# T-Board-44-84_PCB_-_v0_1.net
KiCad netlist of a schematic drawn in EAGLE
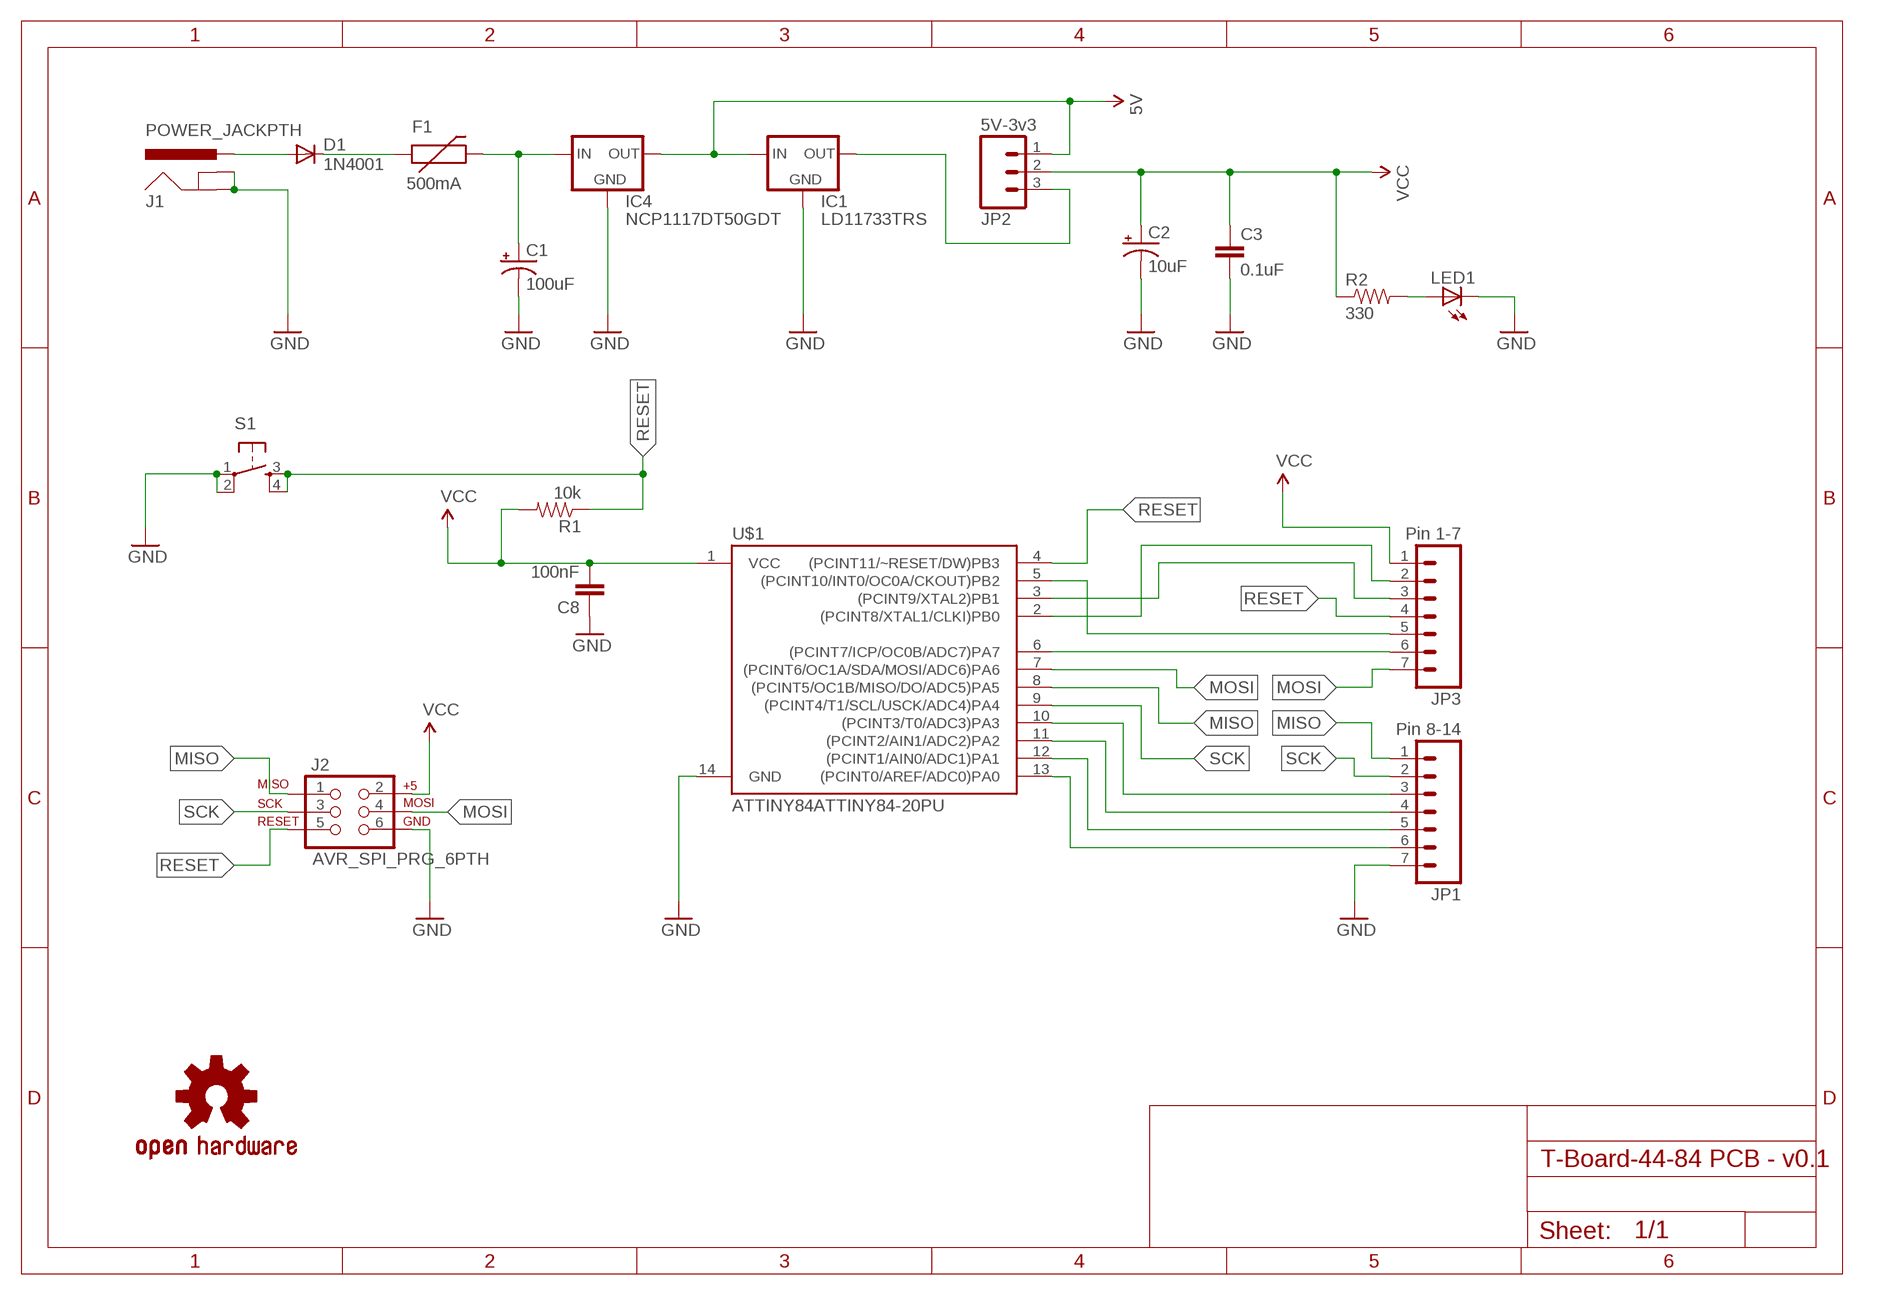
[diagram p0: schematic, sheet 1]

(export (version "E")
  (design (tool "Eeschema 10.0.6"))
  (components
    (comp (ref "C1")
      (value "100uF")
      (footprint "eagle-import:CPOL-RADIAL-100UF-25V")
      (libsource (lib "eagle-import") (part "CAP_POLPTH1"))
    )
    (comp (ref "C2")
      (value "10uF")
      (footprint "eagle-import:CPOL-RADIAL-10UF-25V")
      (libsource (lib "eagle-import") (part "CAP_POLPTH2"))
    )
    (comp (ref "C3")
      (value "0.1uF")
      (footprint "eagle-import:1206")
      (libsource (lib "eagle-import") (part "CAP1206"))
    )
    (comp (ref "C8")
      (value "100nF")
      (footprint "eagle-import:1206")
      (libsource (lib "eagle-import") (part "CAP1206"))
    )
    (comp (ref "D1")
      (value "1N4001")
      (footprint "eagle-import:DIODE-1N4001")
      (libsource (lib "eagle-import") (part "DIODEPTH"))
    )
    (comp (ref "F1")
      (value "500mA")
      (footprint "eagle-import:PTC")
      (libsource (lib "eagle-import") (part "PTCPTH"))
    )
    (comp (ref "IC1")
      (value "LD11733TRS")
      (footprint "eagle-import:SOT223")
      (libsource (lib "eagle-import") (part "LD117S33TR"))
    )
    (comp (ref "IC4")
      (value "NCP1117DT50GDT")
      (footprint "eagle-import:DPACK")
      (libsource (lib "eagle-import") (part "NCP1117DTDT50G"))
    )
    (comp (ref "J1")
      (value "POWER_JACKPTH")
      (footprint "eagle-import:POWER_JACK_PTH")
      (libsource (lib "eagle-import") (part "POWER_JACKPTH"))
    )
    (comp (ref "J2")
      (value "AVR_SPI_PRG_6PTH")
      (footprint "eagle-import:2X3")
      (libsource (lib "eagle-import") (part "AVR_SPI_PRG_6PTH"))
    )
    (comp (ref "JP1")
      (value "Pin 8-14")
      (footprint "eagle-import:1X07")
      (libsource (lib "eagle-import") (part "M07"))
    )
    (comp (ref "JP2")
      (value "5V-3v3")
      (footprint "eagle-import:1X03")
      (libsource (lib "eagle-import") (part "M03PTH"))
    )
    (comp (ref "JP3")
      (value "Pin 1-7")
      (footprint "eagle-import:1X07")
      (libsource (lib "eagle-import") (part "M07"))
    )
    (comp (ref "LED1")
      (value "LED1206")
      (footprint "eagle-import:LED-1206")
      (libsource (lib "eagle-import") (part "LED1206"))
    )
    (comp (ref "LOGO1")
      (value "OSHW-LOGOS")
      (footprint "eagle-import:OSHW-LOGO-S")
      (libsource (lib "eagle-import") (part "OSHW-LOGOS"))
    )
    (comp (ref "R1")
      (value "10k")
      (footprint "eagle-import:1206")
      (libsource (lib "eagle-import") (part "RESISTOR1206"))
    )
    (comp (ref "R2")
      (value "330")
      (footprint "eagle-import:1206")
      (libsource (lib "eagle-import") (part "RESISTOR1206"))
    )
    (comp (ref "S1")
      (value "TAC_SWITCHPTH")
      (footprint "eagle-import:TACTILE-PTH")
      (libsource (lib "eagle-import") (part "TAC_SWITCHPTH"))
    )
    (comp (ref "U$1")
      (value "ATTINY84ATTINY84-20PU")
      (footprint "eagle-import:DIL14")
      (libsource (lib "eagle-import") (part "ATTINY84ATTINY84-20PU"))
    )
  )
  (nets
    (net (code "1") (name "5V") (class "Default")
      (node (ref "IC1") (pin "3") (pinfunction "IN_3") (pintype "input"))
      (node (ref "IC4") (pin "4") (pinfunction "OUT_4") (pintype "passive"))
      (node (ref "JP2") (pin "1") (pinfunction "1_1") (pintype "passive"))
    )
    (net (code "2") (name "GND") (class "Default")
      (node (ref "C1") (pin "2") (pinfunction "-_2") (pintype "passive"))
      (node (ref "C2") (pin "2") (pinfunction "-_2") (pintype "passive"))
      (node (ref "C3") (pin "2") (pinfunction "2_2") (pintype "passive"))
      (node (ref "C8") (pin "1") (pinfunction "1_1") (pintype "passive"))
      (node (ref "IC1") (pin "1") (pinfunction "GND_1") (pintype "input"))
      (node (ref "IC4") (pin "1") (pinfunction "GND_1") (pintype "input"))
      (node (ref "J1") (pin "GND") (pinfunction "GND_GND") (pintype "bidirectional"))
      (node (ref "J1") (pin "GNDBREAK") (pinfunction "GNDBREAK_GNDBREAK") (pintype "bidirectional"))
      (node (ref "J2") (pin "6") (pinfunction "6_6") (pintype "passive"))
      (node (ref "JP1") (pin "7") (pinfunction "7_7") (pintype "passive"))
      (node (ref "LED1") (pin "C") (pinfunction "C_C") (pintype "passive"))
      (node (ref "S1") (pin "1") (pinfunction "1_1") (pintype "passive"))
      (node (ref "S1") (pin "2") (pinfunction "2_2") (pintype "passive"))
      (node (ref "U$1") (pin "14") (pinfunction "GND_14") (pintype "bidirectional"))
    )
    (net (code "3") (name "MISO") (class "Default")
      (node (ref "J2") (pin "1") (pinfunction "1_1") (pintype "passive"))
      (node (ref "JP1") (pin "1") (pinfunction "1_1") (pintype "passive"))
      (node (ref "U$1") (pin "8") (pinfunction "(PCINT5/OC1B/MISO/DO/ADC5)PA5_8") (pintype "bidirectional"))
    )
    (net (code "4") (name "MOSI") (class "Default")
      (node (ref "J2") (pin "4") (pinfunction "4_4") (pintype "passive"))
      (node (ref "JP3") (pin "7") (pinfunction "7_7") (pintype "passive"))
      (node (ref "U$1") (pin "7") (pinfunction "(PCINT6/OC1A/SDA/MOSI/ADC6)PA6_7") (pintype "bidirectional"))
    )
    (net (code "5") (name "Net-(C1-+)") (class "Default")
      (node (ref "C1") (pin "1") (pinfunction "+_1") (pintype "passive"))
      (node (ref "F1") (pin "P$2") (pinfunction "2_P$2") (pintype "bidirectional"))
      (node (ref "IC4") (pin "3") (pinfunction "IN_3") (pintype "input"))
    )
    (net (code "6") (name "Net-(D1-PadA)") (class "Default")
      (node (ref "D1") (pin "A") (pinfunction "A_A") (pintype "passive"))
      (node (ref "J1") (pin "PWR") (pinfunction "PWR_PWR") (pintype "bidirectional"))
    )
    (net (code "7") (name "Net-(F1-1)") (class "Default")
      (node (ref "D1") (pin "C") (pinfunction "C_C") (pintype "passive"))
      (node (ref "F1") (pin "P$1") (pinfunction "1_P$1") (pintype "bidirectional"))
    )
    (net (code "8") (name "Net-(IC1-OUT)") (class "Default")
      (node (ref "IC1") (pin "4") (pinfunction "OUT_4") (pintype "passive"))
      (node (ref "JP2") (pin "3") (pinfunction "3_3") (pintype "passive"))
    )
    (net (code "9") (name "Net-(LED1-PadA)") (class "Default")
      (node (ref "LED1") (pin "A") (pinfunction "A_A") (pintype "passive"))
      (node (ref "R2") (pin "2") (pinfunction "2_2") (pintype "passive"))
    )
    (net (code "10") (name "Net-(U$1-(PCINT0{slash}AREF{slash}ADC0)PA0)") (class "Default")
      (node (ref "JP1") (pin "6") (pinfunction "6_6") (pintype "passive"))
      (node (ref "U$1") (pin "13") (pinfunction "(PCINT0/AREF/ADC0)PA0_13") (pintype "bidirectional"))
    )
    (net (code "11") (name "Net-(U$1-(PCINT1{slash}AIN0{slash}ADC1)PA1)") (class "Default")
      (node (ref "JP1") (pin "5") (pinfunction "5_5") (pintype "passive"))
      (node (ref "U$1") (pin "12") (pinfunction "(PCINT1/AIN0/ADC1)PA1_12") (pintype "bidirectional"))
    )
    (net (code "12") (name "Net-(U$1-(PCINT2{slash}AIN1{slash}ADC2)PA2)") (class "Default")
      (node (ref "JP1") (pin "4") (pinfunction "4_4") (pintype "passive"))
      (node (ref "U$1") (pin "11") (pinfunction "(PCINT2/AIN1/ADC2)PA2_11") (pintype "bidirectional"))
    )
    (net (code "13") (name "Net-(U$1-(PCINT3{slash}T0{slash}ADC3)PA3)") (class "Default")
      (node (ref "JP1") (pin "3") (pinfunction "3_3") (pintype "passive"))
      (node (ref "U$1") (pin "10") (pinfunction "(PCINT3/T0/ADC3)PA3_10") (pintype "bidirectional"))
    )
    (net (code "14") (name "Net-(U$1-(PCINT7{slash}ICP{slash}OC0B{slash}ADC7)PA7)") (class "Default")
      (node (ref "JP3") (pin "6") (pinfunction "6_6") (pintype "passive"))
      (node (ref "U$1") (pin "6") (pinfunction "(PCINT7/ICP/OC0B/ADC7)PA7_6") (pintype "bidirectional"))
    )
    (net (code "15") (name "Net-(U$1-(PCINT8{slash}XTAL1{slash}CLKI)PB0)") (class "Default")
      (node (ref "JP3") (pin "2") (pinfunction "2_2") (pintype "passive"))
      (node (ref "U$1") (pin "2") (pinfunction "(PCINT8/XTAL1/CLKI)PB0_2") (pintype "bidirectional"))
    )
    (net (code "16") (name "Net-(U$1-(PCINT9{slash}XTAL2)PB1)") (class "Default")
      (node (ref "JP3") (pin "3") (pinfunction "3_3") (pintype "passive"))
      (node (ref "U$1") (pin "3") (pinfunction "(PCINT9/XTAL2)PB1_3") (pintype "bidirectional"))
    )
    (net (code "17") (name "Net-(U$1-(PCINT10{slash}INT0{slash}OC0A{slash}CKOUT)PB2)") (class "Default")
      (node (ref "JP3") (pin "5") (pinfunction "5_5") (pintype "passive"))
      (node (ref "U$1") (pin "5") (pinfunction "(PCINT10/INT0/OC0A/CKOUT)PB2_5") (pintype "bidirectional"))
    )
    (net (code "18") (name "RESET") (class "Default")
      (node (ref "J2") (pin "5") (pinfunction "5_5") (pintype "passive"))
      (node (ref "JP3") (pin "4") (pinfunction "4_4") (pintype "passive"))
      (node (ref "R1") (pin "1") (pinfunction "1_1") (pintype "passive"))
      (node (ref "S1") (pin "3") (pinfunction "3_3") (pintype "passive"))
      (node (ref "S1") (pin "4") (pinfunction "4_4") (pintype "passive"))
      (node (ref "U$1") (pin "4") (pinfunction "(PCINT11/~{RESET/DW})PB3_4") (pintype "bidirectional"))
    )
    (net (code "19") (name "SCK") (class "Default")
      (node (ref "J2") (pin "3") (pinfunction "3_3") (pintype "passive"))
      (node (ref "JP1") (pin "2") (pinfunction "2_2") (pintype "passive"))
      (node (ref "U$1") (pin "9") (pinfunction "(PCINT4/T1/SCL/USCK/ADC4)PA4_9") (pintype "bidirectional"))
    )
    (net (code "20") (name "VCC") (class "Default")
      (node (ref "C2") (pin "1") (pinfunction "+_1") (pintype "passive"))
      (node (ref "C3") (pin "1") (pinfunction "1_1") (pintype "passive"))
      (node (ref "C8") (pin "2") (pinfunction "2_2") (pintype "passive"))
      (node (ref "J2") (pin "2") (pinfunction "2_2") (pintype "passive"))
      (node (ref "JP2") (pin "2") (pinfunction "2_2") (pintype "passive"))
      (node (ref "JP3") (pin "1") (pinfunction "1_1") (pintype "passive"))
      (node (ref "R1") (pin "2") (pinfunction "2_2") (pintype "passive"))
      (node (ref "R2") (pin "1") (pinfunction "1_1") (pintype "passive"))
      (node (ref "U$1") (pin "1") (pinfunction "VCC_1") (pintype "bidirectional"))
    )
  )
)
